# alu_mux_schem.net
KiCad netlist of a schematic drawn in Altium Designer
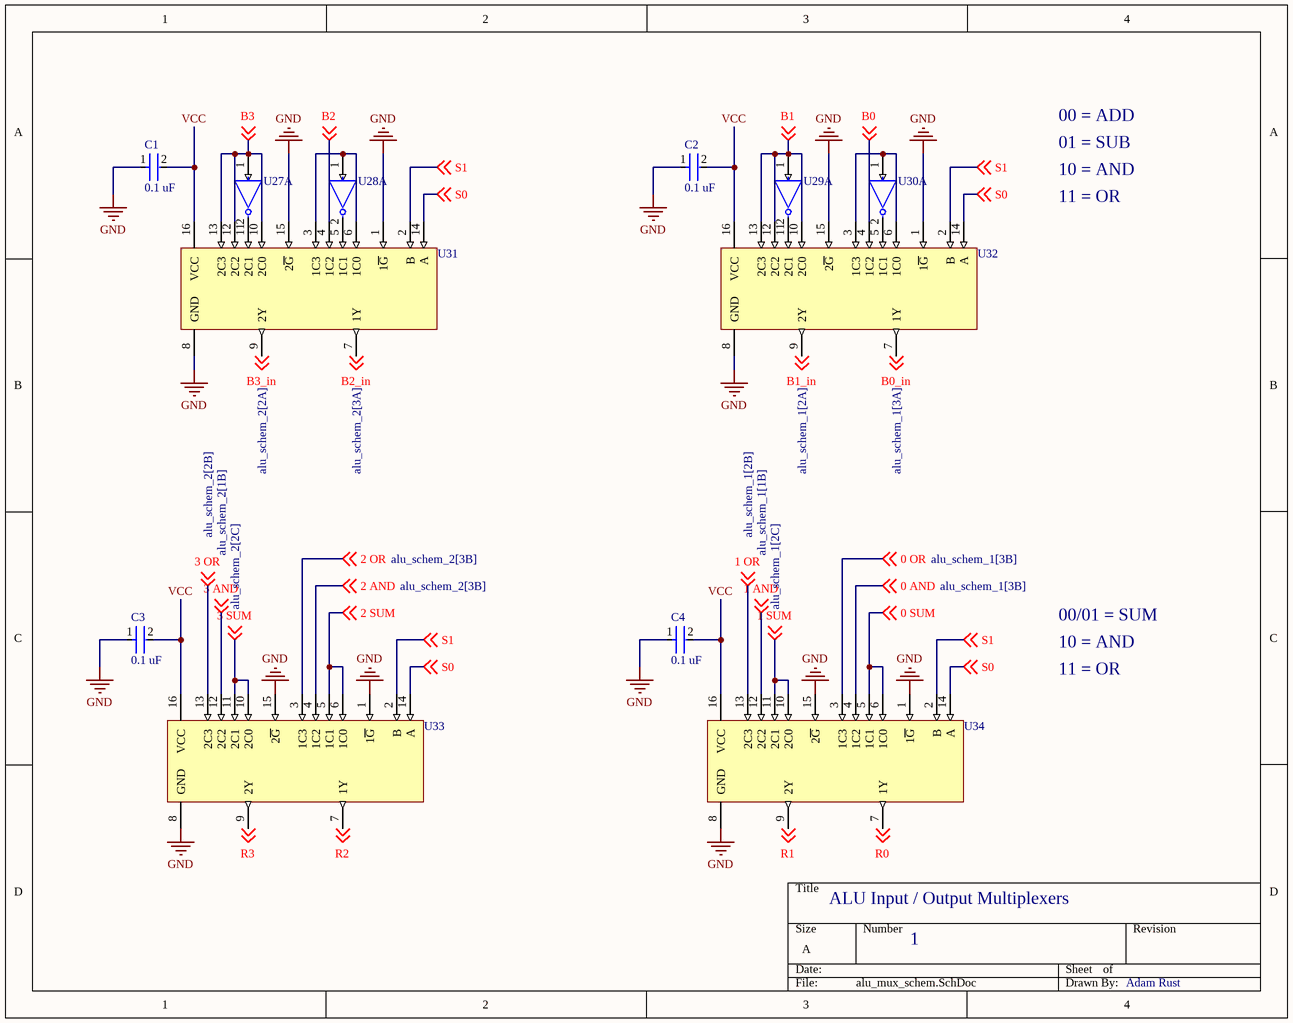
[diagram p0: alu_mux_schem.SchDoc]

(export (version "E")
  (design (tool "Eeschema 10.0.6"))
  (components
    (comp (ref "C1")
      (value "0.1 uF")
      (footprint "FP-GRM022-0_02-MFG")
      (description "GRM022R61C104ME05L Multilayer Ceramic Capacitor, 0.1 uF, 16 V, ± 20%, X5R, 01005 [0402 Metric]")
      (fields (field (name "TOLERANCE") "20%"))
      (libsource (lib "Altium Content Vault") (part "11868f565c42a9108669ba33697ecf6"))
    )
    (comp (ref "C2")
      (value "0.1 uF")
      (footprint "FP-GRM022-0_02-MFG")
      (description "GRM022R61C104ME05L Multilayer Ceramic Capacitor, 0.1 uF, 16 V, ± 20%, X5R, 01005 [0402 Metric]")
      (fields (field (name "TOLERANCE") "20%"))
      (libsource (lib "Altium Content Vault") (part "11868f565c42a9108669ba33697ecf6"))
    )
    (comp (ref "C3")
      (value "0.1 uF")
      (footprint "FP-GRM022-0_02-MFG")
      (description "GRM022R61C104ME05L Multilayer Ceramic Capacitor, 0.1 uF, 16 V, ± 20%, X5R, 01005 [0402 Metric]")
      (fields (field (name "TOLERANCE") "20%"))
      (libsource (lib "Altium Content Vault") (part "11868f565c42a9108669ba33697ecf6"))
    )
    (comp (ref "C4")
      (value "0.1 uF")
      (footprint "FP-GRM022-0_02-MFG")
      (description "GRM022R61C104ME05L Multilayer Ceramic Capacitor, 0.1 uF, 16 V, ± 20%, X5R, 01005 [0402 Metric]")
      (fields (field (name "TOLERANCE") "20%"))
      (libsource (lib "Altium Content Vault") (part "11868f565c42a9108669ba33697ecf6"))
    )
    (comp (ref "U27")
      (value "SN74LVC04ADR")
      (footprint "FP-D0014A-IPC_A")
      (description "IC INVERTER 6CH 6-INP 14SOIC")
      (libsource (lib "Altium Content Vault") (part "709a8d2d34fac73d54705890335673b"))
    )
    (comp (ref "U28")
      (value "SN74LVC04ADR")
      (footprint "FP-D0014A-IPC_A")
      (description "IC INVERTER 6CH 6-INP 14SOIC")
      (libsource (lib "Altium Content Vault") (part "709a8d2d34fac73d54705890335673b"))
    )
    (comp (ref "U29")
      (value "SN74LVC04ADR")
      (footprint "FP-D0014A-IPC_A")
      (description "IC INVERTER 6CH 6-INP 14SOIC")
      (libsource (lib "Altium Content Vault") (part "709a8d2d34fac73d54705890335673b"))
    )
    (comp (ref "U30")
      (value "SN74LVC04ADR")
      (footprint "FP-D0014A-IPC_A")
      (description "IC INVERTER 6CH 6-INP 14SOIC")
      (libsource (lib "Altium Content Vault") (part "709a8d2d34fac73d54705890335673b"))
    )
    (comp (ref "U31")
      (value "SN74HC153DR")
      (footprint "D0016A_N")
      (description "Dual 4-Line To 1-Line Data Selectors/Multiplexers, D0016A, LARGE T&R")
      (fields
        (field (name "MANUFACTURER") "Texas Instruments")
        (field (name "GENERIC PART NUMBER") "SN74HC153")
      )
      (libsource (lib "Altium Content Vault") (part "TI-XXXXXXX153-16"))
    )
    (comp (ref "U32")
      (value "SN74HC153DR")
      (footprint "D0016A_N")
      (description "Dual 4-Line To 1-Line Data Selectors/Multiplexers, D0016A, LARGE T&R")
      (fields
        (field (name "MANUFACTURER") "Texas Instruments")
        (field (name "GENERIC PART NUMBER") "SN74HC153")
      )
      (libsource (lib "Altium Content Vault") (part "TI-XXXXXXX153-16"))
    )
    (comp (ref "U33")
      (value "SN74HC153DR")
      (footprint "D0016A_N")
      (description "Dual 4-Line To 1-Line Data Selectors/Multiplexers, D0016A, LARGE T&R")
      (fields
        (field (name "MANUFACTURER") "Texas Instruments")
        (field (name "GENERIC PART NUMBER") "SN74HC153")
      )
      (libsource (lib "Altium Content Vault") (part "TI-XXXXXXX153-16"))
    )
    (comp (ref "U34")
      (value "SN74HC153DR")
      (footprint "D0016A_N")
      (description "Dual 4-Line To 1-Line Data Selectors/Multiplexers, D0016A, LARGE T&R")
      (fields
        (field (name "MANUFACTURER") "Texas Instruments")
        (field (name "GENERIC PART NUMBER") "SN74HC153")
      )
      (libsource (lib "Altium Content Vault") (part "TI-XXXXXXX153-16"))
    )
  )
  (nets
    (net (code "1") (name "/VCC") (class "Default")
      (node (ref "C1") (pin "2") (pinfunction "2_2") (pintype "passive"))
      (node (ref "C2") (pin "2") (pinfunction "2_2") (pintype "passive"))
      (node (ref "C3") (pin "2") (pinfunction "2_2") (pintype "passive"))
      (node (ref "C4") (pin "2") (pinfunction "2_2") (pintype "passive"))
      (node (ref "U31") (pin "16") (pinfunction "VCC_16") (pintype "power_in"))
      (node (ref "U32") (pin "16") (pinfunction "VCC_16") (pintype "power_in"))
      (node (ref "U33") (pin "16") (pinfunction "VCC_16") (pintype "power_in"))
      (node (ref "U34") (pin "16") (pinfunction "VCC_16") (pintype "power_in"))
    )
    (net (code "2") (name "0 AND") (class "Default")
      (node (ref "U34") (pin "4") (pinfunction "1C2_4") (pintype "input"))
    )
    (net (code "3") (name "0 OR") (class "Default")
      (node (ref "U34") (pin "3") (pinfunction "1C3_3") (pintype "input"))
    )
    (net (code "4") (name "0 SUM") (class "Default")
      (node (ref "U34") (pin "5") (pinfunction "1C1_5") (pintype "input"))
      (node (ref "U34") (pin "6") (pinfunction "1C0_6") (pintype "input"))
    )
    (net (code "5") (name "1 AND") (class "Default")
      (node (ref "U34") (pin "12") (pinfunction "2C2_12") (pintype "input"))
    )
    (net (code "6") (name "1 OR") (class "Default")
      (node (ref "U34") (pin "13") (pinfunction "2C3_13") (pintype "input"))
    )
    (net (code "7") (name "1 SUM") (class "Default")
      (node (ref "U34") (pin "10") (pinfunction "2C0_10") (pintype "input"))
      (node (ref "U34") (pin "11") (pinfunction "2C1_11") (pintype "input"))
    )
    (net (code "8") (name "2 AND") (class "Default")
      (node (ref "U33") (pin "4") (pinfunction "1C2_4") (pintype "input"))
    )
    (net (code "9") (name "2 OR") (class "Default")
      (node (ref "U33") (pin "3") (pinfunction "1C3_3") (pintype "input"))
    )
    (net (code "10") (name "2 SUM") (class "Default")
      (node (ref "U33") (pin "5") (pinfunction "1C1_5") (pintype "input"))
      (node (ref "U33") (pin "6") (pinfunction "1C0_6") (pintype "input"))
    )
    (net (code "11") (name "3 AND") (class "Default")
      (node (ref "U33") (pin "12") (pinfunction "2C2_12") (pintype "input"))
    )
    (net (code "12") (name "3 OR") (class "Default")
      (node (ref "U33") (pin "13") (pinfunction "2C3_13") (pintype "input"))
    )
    (net (code "13") (name "3 SUM") (class "Default")
      (node (ref "U33") (pin "10") (pinfunction "2C0_10") (pintype "input"))
      (node (ref "U33") (pin "11") (pinfunction "2C1_11") (pintype "input"))
    )
    (net (code "14") (name "B0") (class "Default")
      (node (ref "U32") (pin "4") (pinfunction "1C2_4") (pintype "input"))
    )
    (net (code "15") (name "B0_in") (class "Default")
      (node (ref "U32") (pin "7") (pinfunction "1Y_7") (pintype "output"))
    )
    (net (code "16") (name "B1") (class "Default")
      (node (ref "U29") (pin "1") (pinfunction "1A_1") (pintype "input"))
      (node (ref "U32") (pin "10") (pinfunction "2C0_10") (pintype "input"))
      (node (ref "U32") (pin "12") (pinfunction "2C2_12") (pintype "input"))
      (node (ref "U32") (pin "13") (pinfunction "2C3_13") (pintype "input"))
    )
    (net (code "17") (name "B1_in") (class "Default")
      (node (ref "U32") (pin "9") (pinfunction "2Y_9") (pintype "output"))
    )
    (net (code "18") (name "B2") (class "Default")
      (node (ref "U31") (pin "4") (pinfunction "1C2_4") (pintype "input"))
    )
    (net (code "19") (name "B2_in") (class "Default")
      (node (ref "U31") (pin "7") (pinfunction "1Y_7") (pintype "output"))
    )
    (net (code "20") (name "B3") (class "Default")
      (node (ref "U27") (pin "1") (pinfunction "1A_1") (pintype "input"))
      (node (ref "U31") (pin "10") (pinfunction "2C0_10") (pintype "input"))
      (node (ref "U31") (pin "12") (pinfunction "2C2_12") (pintype "input"))
      (node (ref "U31") (pin "13") (pinfunction "2C3_13") (pintype "input"))
    )
    (net (code "21") (name "B3_in") (class "Default")
      (node (ref "U31") (pin "9") (pinfunction "2Y_9") (pintype "output"))
    )
    (net (code "22") (name "GND") (class "Default")
      (node (ref "C1") (pin "1") (pinfunction "1_1") (pintype "passive"))
      (node (ref "C2") (pin "1") (pinfunction "1_1") (pintype "passive"))
      (node (ref "C3") (pin "1") (pinfunction "1_1") (pintype "passive"))
      (node (ref "C4") (pin "1") (pinfunction "1_1") (pintype "passive"))
      (node (ref "U31") (pin "1") (pinfunction "1~{G}_1") (pintype "input"))
      (node (ref "U31") (pin "15") (pinfunction "2~{G}_15") (pintype "input"))
      (node (ref "U31") (pin "8") (pinfunction "GND_8") (pintype "power_in"))
      (node (ref "U32") (pin "1") (pinfunction "1~{G}_1") (pintype "input"))
      (node (ref "U32") (pin "15") (pinfunction "2~{G}_15") (pintype "input"))
      (node (ref "U32") (pin "8") (pinfunction "GND_8") (pintype "power_in"))
      (node (ref "U33") (pin "1") (pinfunction "1~{G}_1") (pintype "input"))
      (node (ref "U33") (pin "15") (pinfunction "2~{G}_15") (pintype "input"))
      (node (ref "U33") (pin "8") (pinfunction "GND_8") (pintype "power_in"))
      (node (ref "U34") (pin "1") (pinfunction "1~{G}_1") (pintype "input"))
      (node (ref "U34") (pin "15") (pinfunction "2~{G}_15") (pintype "input"))
      (node (ref "U34") (pin "8") (pinfunction "GND_8") (pintype "power_in"))
    )
    (net (code "23") (name "Net-(U27A-1Y)") (class "Default")
      (node (ref "U27") (pin "2") (pinfunction "1Y_2") (pintype "output"))
      (node (ref "U31") (pin "11") (pinfunction "2C1_11") (pintype "input"))
    )
    (net (code "24") (name "Net-(U28A-1A)") (class "Default")
      (node (ref "U28") (pin "1") (pinfunction "1A_1") (pintype "input"))
      (node (ref "U31") (pin "3") (pinfunction "1C3_3") (pintype "input"))
      (node (ref "U31") (pin "6") (pinfunction "1C0_6") (pintype "input"))
    )
    (net (code "25") (name "Net-(U28A-1Y)") (class "Default")
      (node (ref "U28") (pin "2") (pinfunction "1Y_2") (pintype "output"))
      (node (ref "U31") (pin "5") (pinfunction "1C1_5") (pintype "input"))
    )
    (net (code "26") (name "Net-(U29A-1Y)") (class "Default")
      (node (ref "U29") (pin "2") (pinfunction "1Y_2") (pintype "output"))
      (node (ref "U32") (pin "11") (pinfunction "2C1_11") (pintype "input"))
    )
    (net (code "27") (name "Net-(U30A-1A)") (class "Default")
      (node (ref "U30") (pin "1") (pinfunction "1A_1") (pintype "input"))
      (node (ref "U32") (pin "3") (pinfunction "1C3_3") (pintype "input"))
      (node (ref "U32") (pin "6") (pinfunction "1C0_6") (pintype "input"))
    )
    (net (code "28") (name "Net-(U30A-1Y)") (class "Default")
      (node (ref "U30") (pin "2") (pinfunction "1Y_2") (pintype "output"))
      (node (ref "U32") (pin "5") (pinfunction "1C1_5") (pintype "input"))
    )
    (net (code "29") (name "R0") (class "Default")
      (node (ref "U34") (pin "7") (pinfunction "1Y_7") (pintype "output"))
    )
    (net (code "30") (name "R1") (class "Default")
      (node (ref "U34") (pin "9") (pinfunction "2Y_9") (pintype "output"))
    )
    (net (code "31") (name "R2") (class "Default")
      (node (ref "U33") (pin "7") (pinfunction "1Y_7") (pintype "output"))
    )
    (net (code "32") (name "R3") (class "Default")
      (node (ref "U33") (pin "9") (pinfunction "2Y_9") (pintype "output"))
    )
    (net (code "33") (name "S0") (class "Default")
      (node (ref "U31") (pin "14") (pinfunction "A_14") (pintype "input"))
      (node (ref "U32") (pin "14") (pinfunction "A_14") (pintype "input"))
      (node (ref "U33") (pin "14") (pinfunction "A_14") (pintype "input"))
      (node (ref "U34") (pin "14") (pinfunction "A_14") (pintype "input"))
    )
    (net (code "34") (name "S1") (class "Default")
      (node (ref "U31") (pin "2") (pinfunction "B_2") (pintype "input"))
      (node (ref "U32") (pin "2") (pinfunction "B_2") (pintype "input"))
      (node (ref "U33") (pin "2") (pinfunction "B_2") (pintype "input"))
      (node (ref "U34") (pin "2") (pinfunction "B_2") (pintype "input"))
    )
  )
)
